# OTP6.net
KiCad netlist of a schematic drawn in Altium Designer
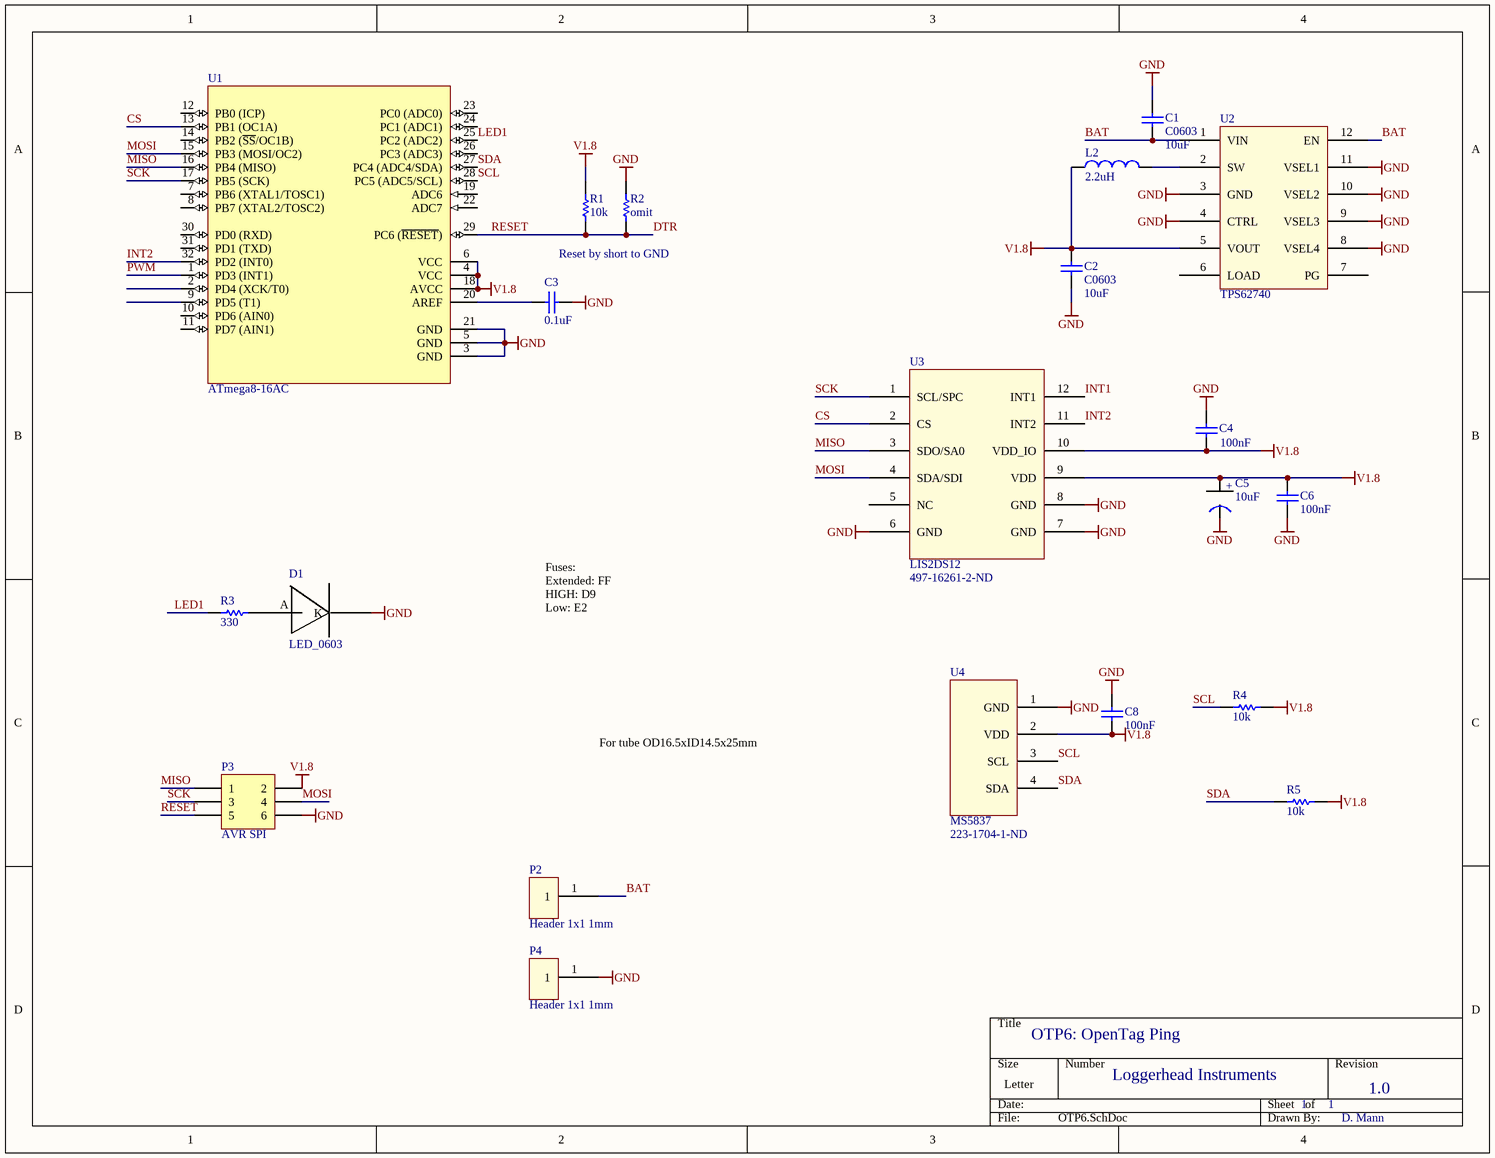
[diagram p0: OTP6.SchDoc]

(export (version "E")
  (design (tool "Eeschema 10.0.6"))
  (components
    (comp (ref "C1")
      (value "C0603")
      (footprint "0603")
      (description "Ceramic Chip Capacitor - Standard")
      (fields (field (name "ALTIUM_VALUE") "10uF") (field (name "PUBLISHER") "Altium Limited"))
      (libsource (lib "KEMET Chip Capacitor") (part "C0603"))
    )
    (comp (ref "C2")
      (value "C0603")
      (footprint "0603")
      (description "Ceramic Chip Capacitor - Standard")
      (fields (field (name "ALTIUM_VALUE") "10uF") (field (name "PUBLISHER") "Altium Limited"))
      (libsource (lib "KEMET Chip Capacitor") (part "C0603"))
    )
    (comp (ref "C3")
      (value "0.1uF")
      (footprint "0402")
      (description "Ceramic Chip Capacitor - Standard")
      (fields (field (name "PUBLISHER") "Altium Limited"))
      (libsource (lib "KEMET Chip Capacitor") (part "C0402"))
    )
    (comp (ref "C4")
      (value "100nF")
      (footprint "0402")
      (description "Ceramic Chip Capacitor - Standard")
      (fields (field (name "PUBLISHER") "Altium Limited"))
      (libsource (lib "KEMET Chip Capacitor") (part "C0402"))
    )
    (comp (ref "C5") (value "10uF") (footprint "Tant0805") (libsource (lib "Loggerhead") (part "Tant0805")))
    (comp (ref "C6")
      (value "100nF")
      (footprint "0402")
      (description "Ceramic Chip Capacitor - Standard")
      (fields (field (name "PUBLISHER") "Altium Limited"))
      (libsource (lib "KEMET Chip Capacitor") (part "C0402"))
    )
    (comp (ref "C8")
      (value "100nF")
      (footprint "0402")
      (description "Ceramic Chip Capacitor - Standard")
      (fields (field (name "PUBLISHER") "Altium Limited"))
      (libsource (lib "KEMET Chip Capacitor") (part "C0402"))
    )
    (comp (ref "D1")
      (value "LED_0603")
      (footprint "Diode0603")
      (libsource (lib "Loggerhead") (part "LED_0603"))
    )
    (comp (ref "L2")
      (value "2.2uH")
      (footprint "Inductor KLZ1608AHR")
      (libsource (lib "Loggerhead") (part "Inductor KLZ1608"))
    )
    (comp (ref "P2")
      (value "Header 1x1 1mm")
      (footprint "Header1x1mm")
      (description "1mm through hole")
      (libsource (lib "Loggerhead") (part "Header 1x1 1mm"))
    )
    (comp (ref "P3")
      (value "AVR SPI")
      (footprint "HDR2X3")
      (description "Header, 3-Pin, Dual row")
      (fields (field (name "PUBLISHER") "Altium Limited"))
      (libsource (lib "Miscellaneous Connectors") (part "Header 3X2"))
    )
    (comp (ref "P4")
      (value "Header 1x1 1mm")
      (footprint "Header1x1mm")
      (description "1mm through hole")
      (libsource (lib "Loggerhead") (part "Header 1x1 1mm"))
    )
    (comp (ref "R1")
      (value "10k")
      (footprint "2-0402")
      (fields (field (name "PUBLISHER") "Altium Limited"))
      (libsource (lib "Panasonic Resistor") (part "ERJ2RB"))
    )
    (comp (ref "R2")
      (value "omit")
      (footprint "3-0603")
      (fields (field (name "PUBLISHER") "Altium Limited"))
      (libsource (lib "Panasonic Resistor") (part "ERJ3RK"))
    )
    (comp (ref "R3")
      (value "330")
      (footprint "2-0402")
      (fields (field (name "PUBLISHER") "Altium Limited"))
      (libsource (lib "Panasonic Resistor") (part "ERJ2RB"))
    )
    (comp (ref "R4")
      (value "10k")
      (footprint "2-0402")
      (fields (field (name "PUBLISHER") "Altium Limited"))
      (libsource (lib "Panasonic Resistor") (part "ERJ2RB"))
    )
    (comp (ref "R5")
      (value "10k")
      (footprint "2-0402")
      (fields (field (name "PUBLISHER") "Altium Limited"))
      (libsource (lib "Panasonic Resistor") (part "ERJ2RB"))
    )
    (comp (ref "U1")
      (value "ATmega8-16AC")
      (footprint "32M1-A_M")
      (description "8-Bit AVR Microcontroller with 8K Bytes of In-System Programmable Flash Memory")
      (fields (field (name "PUBLISHER") "Altium Limited"))
      (libsource (lib "Atmel Microcontroller 8-Bit AVR") (part "ATmega8-16AC"))
    )
    (comp (ref "U2")
      (value "TPS62740")
      (footprint "TPS6274x")
      (libsource (lib "Loggerhead") (part "TPS6274x"))
    )
    (comp (ref "U3")
      (value "LIS2DS12")
      (footprint "LGA-12")
      (fields (field (name "SUPPLIER PART NUMBER 1") "497-16261-2-ND"))
      (libsource (lib "Loggerhead") (part "LIS2DS12"))
    )
    (comp (ref "U4")
      (value "MS5837")
      (footprint "MS5837")
      (description "Pressure/Temp")
      (fields (field (name "SUPPLIER PART NUMBER 1") "223-1704-1-ND"))
      (libsource (lib "Loggerhead") (part "MS5837"))
    )
  )
  (nets
    (net (code "1") (name "/BAT") (class "Default")
      (node (ref "C1") (pin "1") (pinfunction "1_1") (pintype "passive"))
      (node (ref "P2") (pin "1") (pinfunction "1_1") (pintype "passive"))
      (node (ref "U2") (pin "1") (pinfunction "VIN_1") (pintype "passive"))
      (node (ref "U2") (pin "12") (pinfunction "EN_12") (pintype "passive"))
    )
    (net (code "2") (name "/CS") (class "Default")
      (node (ref "U1") (pin "13") (pinfunction "PB1_(OC1A)_13") (pintype "bidirectional"))
      (node (ref "U3") (pin "2") (pinfunction "CS_2") (pintype "passive"))
    )
    (net (code "3") (name "/DTR") (class "Default")
      (node (ref "P3") (pin "5") (pinfunction "5_5") (pintype "passive"))
      (node (ref "R1") (pin "1") (pinfunction "1_1") (pintype "passive"))
      (node (ref "R2") (pin "1") (pinfunction "1_1") (pintype "passive"))
      (node (ref "U1") (pin "29") (pinfunction "PC6_(~{RESET})_29") (pintype "bidirectional"))
    )
    (net (code "4") (name "/INT1") (class "Default")
      (node (ref "U3") (pin "12") (pinfunction "INT1_12") (pintype "passive"))
    )
    (net (code "5") (name "/INT2") (class "Default")
      (node (ref "U1") (pin "32") (pinfunction "PD2_(INT0)_32") (pintype "bidirectional"))
      (node (ref "U3") (pin "11") (pinfunction "INT2_11") (pintype "passive"))
    )
    (net (code "6") (name "/LED1") (class "Default")
      (node (ref "R3") (pin "2") (pinfunction "2_2") (pintype "passive"))
      (node (ref "U1") (pin "25") (pinfunction "PC2_(ADC2)_25") (pintype "bidirectional"))
    )
    (net (code "7") (name "/MISO") (class "Default")
      (node (ref "P3") (pin "1") (pinfunction "1_1") (pintype "passive"))
      (node (ref "U1") (pin "16") (pinfunction "PB4_(MISO)_16") (pintype "bidirectional"))
      (node (ref "U3") (pin "3") (pinfunction "SDO/SA0_3") (pintype "passive"))
    )
    (net (code "8") (name "/MOSI") (class "Default")
      (node (ref "P3") (pin "4") (pinfunction "4_4") (pintype "passive"))
      (node (ref "U1") (pin "15") (pinfunction "PB3_(MOSI/OC2)_15") (pintype "bidirectional"))
      (node (ref "U3") (pin "4") (pinfunction "SDA/SDI_4") (pintype "passive"))
    )
    (net (code "9") (name "/PWM") (class "Default")
      (node (ref "U1") (pin "1") (pinfunction "PD3_(INT1)_1") (pintype "bidirectional"))
    )
    (net (code "10") (name "/SCK") (class "Default")
      (node (ref "P3") (pin "3") (pinfunction "3_3") (pintype "passive"))
      (node (ref "U1") (pin "17") (pinfunction "PB5_(SCK)_17") (pintype "bidirectional"))
      (node (ref "U3") (pin "1") (pinfunction "SCL/SPC_1") (pintype "passive"))
    )
    (net (code "11") (name "/SCL") (class "Default")
      (node (ref "R4") (pin "2") (pinfunction "2_2") (pintype "passive"))
      (node (ref "U1") (pin "28") (pinfunction "PC5_(ADC5/SCL)_28") (pintype "bidirectional"))
      (node (ref "U4") (pin "3") (pinfunction "SCL_3") (pintype "passive"))
    )
    (net (code "12") (name "/SDA") (class "Default")
      (node (ref "R5") (pin "2") (pinfunction "2_2") (pintype "passive"))
      (node (ref "U1") (pin "27") (pinfunction "PC4_(ADC4/SDA)_27") (pintype "bidirectional"))
      (node (ref "U4") (pin "4") (pinfunction "SDA_4") (pintype "passive"))
    )
    (net (code "13") (name "GND") (class "Default")
      (node (ref "C1") (pin "2") (pinfunction "2_2") (pintype "passive"))
      (node (ref "C2") (pin "1") (pinfunction "1_1") (pintype "passive"))
      (node (ref "C3") (pin "2") (pinfunction "2_2") (pintype "passive"))
      (node (ref "C4") (pin "2") (pinfunction "2_2") (pintype "passive"))
      (node (ref "C5") (pin "1") (pinfunction "GND_1") (pintype "passive"))
      (node (ref "C6") (pin "2") (pinfunction "2_2") (pintype "passive"))
      (node (ref "C8") (pin "2") (pinfunction "2_2") (pintype "passive"))
      (node (ref "D1") (pin "K") (pinfunction "K_K") (pintype "passive"))
      (node (ref "P3") (pin "6") (pinfunction "6_6") (pintype "passive"))
      (node (ref "P4") (pin "1") (pinfunction "1_1") (pintype "passive"))
      (node (ref "R2") (pin "2") (pinfunction "2_2") (pintype "passive"))
      (node (ref "U1") (pin "21") (pinfunction "GND_21") (pintype "power_in"))
      (node (ref "U1") (pin "3") (pinfunction "GND_3") (pintype "power_in"))
      (node (ref "U1") (pin "5") (pinfunction "GND_5") (pintype "power_in"))
      (node (ref "U2") (pin "10") (pinfunction "VSEL2_10") (pintype "passive"))
      (node (ref "U2") (pin "11") (pinfunction "VSEL1_11") (pintype "passive"))
      (node (ref "U2") (pin "3") (pinfunction "GND_3") (pintype "passive"))
      (node (ref "U2") (pin "4") (pinfunction "CTRL_4") (pintype "passive"))
      (node (ref "U2") (pin "8") (pinfunction "VSEL4_8") (pintype "passive"))
      (node (ref "U2") (pin "9") (pinfunction "VSEL3_9") (pintype "passive"))
      (node (ref "U3") (pin "6") (pinfunction "GND_6") (pintype "passive"))
      (node (ref "U3") (pin "7") (pinfunction "GND_7") (pintype "passive"))
      (node (ref "U3") (pin "8") (pinfunction "GND_8") (pintype "passive"))
      (node (ref "U4") (pin "1") (pinfunction "GND_1") (pintype "passive"))
    )
    (net (code "14") (name "Net-(D1-PadA)") (class "Default")
      (node (ref "D1") (pin "A") (pinfunction "A_A") (pintype "passive"))
      (node (ref "R3") (pin "1") (pinfunction "1_1") (pintype "passive"))
    )
    (net (code "15") (name "Net-(U1-AREF)") (class "Default")
      (node (ref "C3") (pin "1") (pinfunction "1_1") (pintype "passive"))
      (node (ref "U1") (pin "20") (pinfunction "AREF_20") (pintype "passive"))
    )
    (net (code "16") (name "Net-(U2-SW)") (class "Default")
      (node (ref "L2") (pin "2") (pinfunction "2_2") (pintype "passive"))
      (node (ref "U2") (pin "2") (pinfunction "SW_2") (pintype "passive"))
    )
    (net (code "17") (name "V1.8") (class "Default")
      (node (ref "C2") (pin "2") (pinfunction "2_2") (pintype "passive"))
      (node (ref "C4") (pin "1") (pinfunction "1_1") (pintype "passive"))
      (node (ref "C5") (pin "2") (pinfunction "+_2") (pintype "passive"))
      (node (ref "C6") (pin "1") (pinfunction "1_1") (pintype "passive"))
      (node (ref "C8") (pin "1") (pinfunction "1_1") (pintype "passive"))
      (node (ref "L2") (pin "1") (pinfunction "1_1") (pintype "passive"))
      (node (ref "P3") (pin "2") (pinfunction "2_2") (pintype "passive"))
      (node (ref "R1") (pin "2") (pinfunction "2_2") (pintype "passive"))
      (node (ref "R4") (pin "1") (pinfunction "1_1") (pintype "passive"))
      (node (ref "R5") (pin "1") (pinfunction "1_1") (pintype "passive"))
      (node (ref "U1") (pin "18") (pinfunction "AVCC_18") (pintype "power_in"))
      (node (ref "U1") (pin "4") (pinfunction "VCC_4") (pintype "power_in"))
      (node (ref "U1") (pin "6") (pinfunction "VCC_6") (pintype "power_in"))
      (node (ref "U2") (pin "5") (pinfunction "VOUT_5") (pintype "passive"))
      (node (ref "U3") (pin "10") (pinfunction "VDD_IO_10") (pintype "passive"))
      (node (ref "U3") (pin "9") (pinfunction "VDD_9") (pintype "passive"))
      (node (ref "U4") (pin "2") (pinfunction "VDD_2") (pintype "passive"))
    )
    (net (code "18") (name "unconnected-(U1-ADC6-Pad19)") (class "Default")
      (node (ref "U1") (pin "19") (pinfunction "ADC6_19") (pintype "input"))
    )
    (net (code "19") (name "unconnected-(U1-ADC7-Pad22)") (class "Default")
      (node (ref "U1") (pin "22") (pinfunction "ADC7_22") (pintype "input"))
    )
    (net (code "20") (name "unconnected-(U1-PB0_(ICP)-Pad12)") (class "Default")
      (node (ref "U1") (pin "12") (pinfunction "PB0_(ICP)_12") (pintype "bidirectional"))
    )
    (net (code "21") (name "unconnected-(U1-PB2_(~{SS}{slash}OC1B)-Pad14)") (class "Default")
      (node (ref "U1") (pin "14") (pinfunction "PB2_(~{SS}/OC1B)_14") (pintype "bidirectional"))
    )
    (net (code "22") (name "unconnected-(U1-PB6_(XTAL1{slash}TOSC1)-Pad7)") (class "Default")
      (node (ref "U1") (pin "7") (pinfunction "PB6_(XTAL1/TOSC1)_7") (pintype "bidirectional"))
    )
    (net (code "23") (name "unconnected-(U1-PB7_(XTAL2{slash}TOSC2)-Pad8)") (class "Default")
      (node (ref "U1") (pin "8") (pinfunction "PB7_(XTAL2/TOSC2)_8") (pintype "bidirectional"))
    )
    (net (code "24") (name "unconnected-(U1-PC0_(ADC0)-Pad23)") (class "Default")
      (node (ref "U1") (pin "23") (pinfunction "PC0_(ADC0)_23") (pintype "bidirectional"))
    )
    (net (code "25") (name "unconnected-(U1-PC1_(ADC1)-Pad24)") (class "Default")
      (node (ref "U1") (pin "24") (pinfunction "PC1_(ADC1)_24") (pintype "bidirectional"))
    )
    (net (code "26") (name "unconnected-(U1-PC3_(ADC3)-Pad26)") (class "Default")
      (node (ref "U1") (pin "26") (pinfunction "PC3_(ADC3)_26") (pintype "bidirectional"))
    )
    (net (code "27") (name "unconnected-(U1-PD0_(RXD)-Pad30)") (class "Default")
      (node (ref "U1") (pin "30") (pinfunction "PD0_(RXD)_30") (pintype "bidirectional"))
    )
    (net (code "28") (name "unconnected-(U1-PD1_(TXD)-Pad31)") (class "Default")
      (node (ref "U1") (pin "31") (pinfunction "PD1_(TXD)_31") (pintype "bidirectional"))
    )
    (net (code "29") (name "unconnected-(U1-PD4_(XCK{slash}T0)-Pad2)") (class "Default")
      (node (ref "U1") (pin "2") (pinfunction "PD4_(XCK/T0)_2") (pintype "bidirectional"))
    )
    (net (code "30") (name "unconnected-(U1-PD5_(T1)-Pad9)") (class "Default")
      (node (ref "U1") (pin "9") (pinfunction "PD5_(T1)_9") (pintype "bidirectional"))
    )
    (net (code "31") (name "unconnected-(U1-PD6_(AIN0)-Pad10)") (class "Default")
      (node (ref "U1") (pin "10") (pinfunction "PD6_(AIN0)_10") (pintype "bidirectional"))
    )
    (net (code "32") (name "unconnected-(U1-PD7_(AIN1)-Pad11)") (class "Default")
      (node (ref "U1") (pin "11") (pinfunction "PD7_(AIN1)_11") (pintype "bidirectional"))
    )
    (net (code "33") (name "unconnected-(U2-LOAD-Pad6)") (class "Default")
      (node (ref "U2") (pin "6") (pinfunction "LOAD_6") (pintype "passive"))
    )
    (net (code "34") (name "unconnected-(U2-PG-Pad7)") (class "Default")
      (node (ref "U2") (pin "7") (pinfunction "PG_7") (pintype "passive"))
    )
    (net (code "35") (name "unconnected-(U3-NC-Pad5)") (class "Default")
      (node (ref "U3") (pin "5") (pinfunction "NC_5") (pintype "passive"))
    )
  )
)
